# test-cell-one-shot-rev2.net
KiCad netlist of a schematic drawn in EAGLE
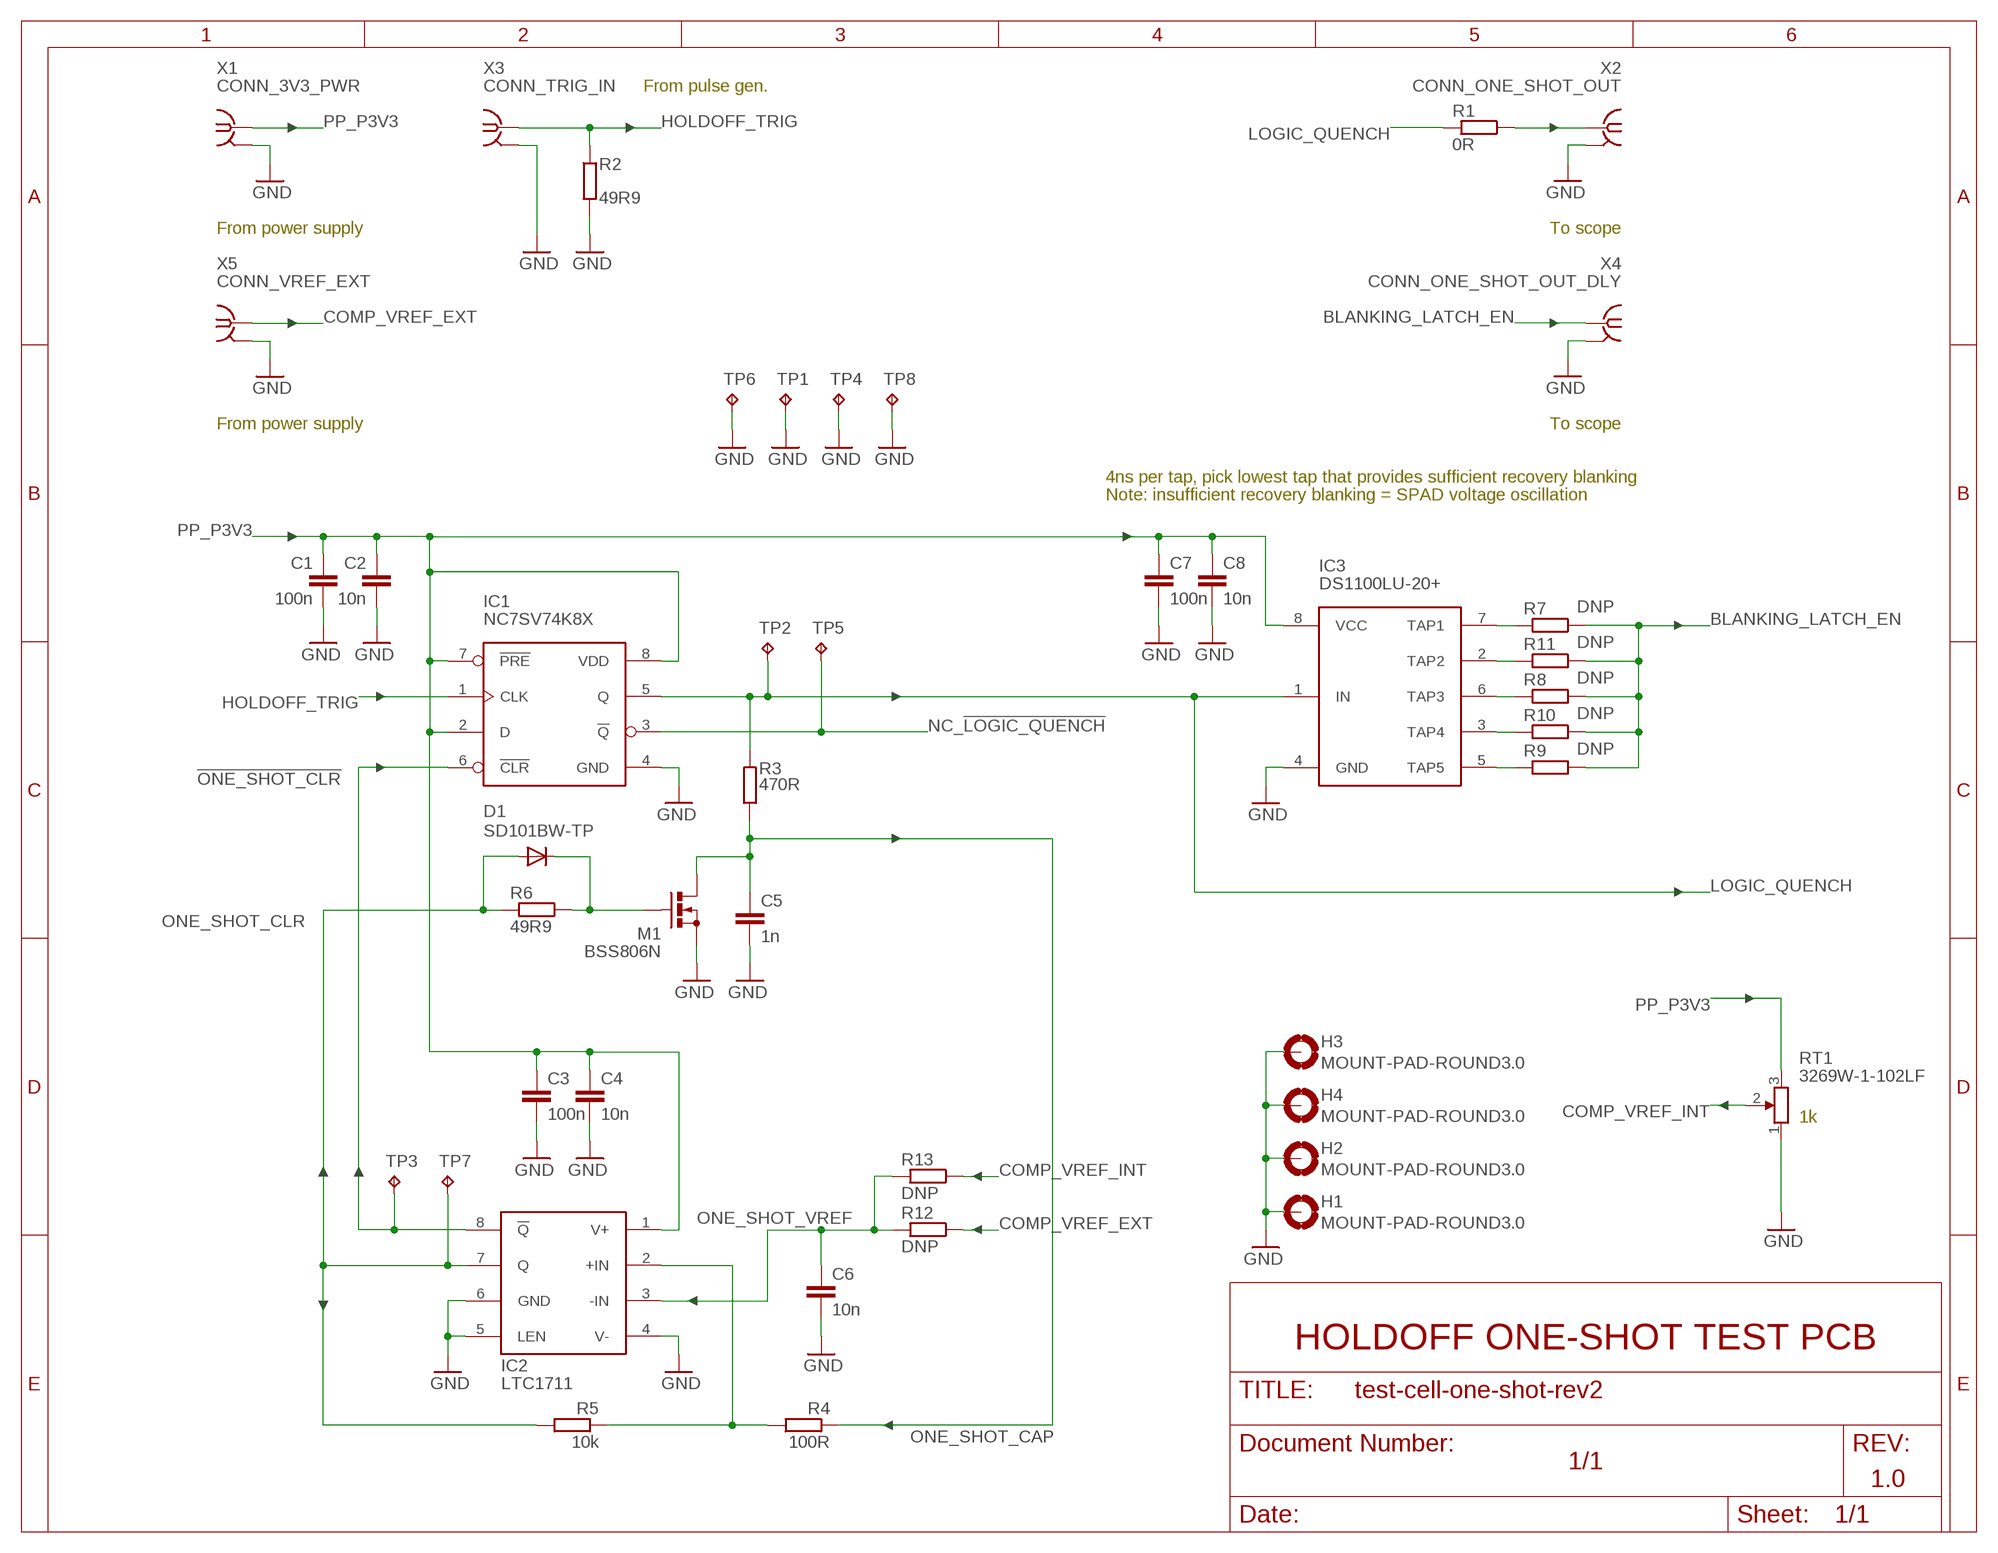
[diagram p0: schematic, sheet 1]

(export (version "E")
  (design (tool "Eeschema 10.0.6"))
  (components
    (comp (ref "C1")
      (value "100n")
      (footprint "eagle-import:C0402")
      (libsource (lib "eagle-import") (part "C-EUC0402"))
    )
    (comp (ref "C2")
      (value "10n")
      (footprint "eagle-import:C0402")
      (libsource (lib "eagle-import") (part "C-EUC0402"))
    )
    (comp (ref "C3")
      (value "100n")
      (footprint "eagle-import:C0402")
      (libsource (lib "eagle-import") (part "C-EUC0402"))
    )
    (comp (ref "C4")
      (value "10n")
      (footprint "eagle-import:C0402")
      (libsource (lib "eagle-import") (part "C-EUC0402"))
    )
    (comp (ref "C5")
      (value "1n")
      (footprint "eagle-import:C0402")
      (libsource (lib "eagle-import") (part "C-EUC0402"))
    )
    (comp (ref "C6")
      (value "10n")
      (footprint "eagle-import:C0402")
      (libsource (lib "eagle-import") (part "C-EUC0402"))
    )
    (comp (ref "C7")
      (value "100n")
      (footprint "eagle-import:C0402")
      (libsource (lib "eagle-import") (part "C-EUC0402"))
    )
    (comp (ref "C8")
      (value "10n")
      (footprint "eagle-import:C0402")
      (libsource (lib "eagle-import") (part "C-EUC0402"))
    )
    (comp (ref "D1")
      (value "SD101BW-TP")
      (footprint "eagle-import:SOD123")
      (libsource (lib "eagle-import") (part "DIODE-SOD123"))
    )
    (comp (ref "H1")
      (value "MOUNT-PAD-ROUND3.0")
      (footprint "eagle-import:3,0-PAD")
      (libsource (lib "eagle-import") (part "MOUNT-PAD-ROUND3.0"))
    )
    (comp (ref "H2")
      (value "MOUNT-PAD-ROUND3.0")
      (footprint "eagle-import:3,0-PAD")
      (libsource (lib "eagle-import") (part "MOUNT-PAD-ROUND3.0"))
    )
    (comp (ref "H3")
      (value "MOUNT-PAD-ROUND3.0")
      (footprint "eagle-import:3,0-PAD")
      (libsource (lib "eagle-import") (part "MOUNT-PAD-ROUND3.0"))
    )
    (comp (ref "H4")
      (value "MOUNT-PAD-ROUND3.0")
      (footprint "eagle-import:3,0-PAD")
      (libsource (lib "eagle-import") (part "MOUNT-PAD-ROUND3.0"))
    )
    (comp (ref "IC1")
      (value "NC7SV74K8X")
      (footprint "eagle-import:US8_3.1MM_JDEC_MO-187")
      (libsource (lib "eagle-import") (part "NC7SV74K8X"))
    )
    (comp (ref "IC2")
      (value "LTC1711")
      (footprint "eagle-import:MSOP8")
      (libsource (lib "eagle-import") (part "LTC1711"))
    )
    (comp (ref "IC3")
      (value "DS1100LU-20+")
      (footprint "eagle-import:MSOP8")
      (libsource (lib "eagle-import") (part "DS1100L"))
    )
    (comp (ref "M1")
      (value "BSS806N")
      (footprint "eagle-import:SOT23R_INFINEON")
      (libsource (lib "eagle-import") (part "BSS806N"))
    )
    (comp (ref "R1")
      (value "0R")
      (footprint "eagle-import:R0402")
      (libsource (lib "eagle-import") (part "R-EU_R0402"))
    )
    (comp (ref "R2")
      (value "49R9")
      (footprint "eagle-import:R0603")
      (libsource (lib "eagle-import") (part "R-EU_R0603"))
    )
    (comp (ref "R3")
      (value "470R")
      (footprint "eagle-import:R0402")
      (libsource (lib "eagle-import") (part "R-EU_R0402"))
    )
    (comp (ref "R4")
      (value "100R")
      (footprint "eagle-import:R0402")
      (libsource (lib "eagle-import") (part "R-EU_R0402"))
    )
    (comp (ref "R5")
      (value "10k")
      (footprint "eagle-import:R0402")
      (libsource (lib "eagle-import") (part "R-EU_R0402"))
    )
    (comp (ref "R6")
      (value "49R9")
      (footprint "eagle-import:R0402")
      (libsource (lib "eagle-import") (part "R-EU_R0402"))
    )
    (comp (ref "R7")
      (value "DNP")
      (footprint "eagle-import:R0402")
      (libsource (lib "eagle-import") (part "R-EU_R0402"))
    )
    (comp (ref "R8")
      (value "DNP")
      (footprint "eagle-import:R0402")
      (libsource (lib "eagle-import") (part "R-EU_R0402"))
    )
    (comp (ref "R9")
      (value "DNP")
      (footprint "eagle-import:R0402")
      (libsource (lib "eagle-import") (part "R-EU_R0402"))
    )
    (comp (ref "R10")
      (value "DNP")
      (footprint "eagle-import:R0402")
      (libsource (lib "eagle-import") (part "R-EU_R0402"))
    )
    (comp (ref "R11")
      (value "DNP")
      (footprint "eagle-import:R0402")
      (libsource (lib "eagle-import") (part "R-EU_R0402"))
    )
    (comp (ref "R12")
      (value "DNP")
      (footprint "eagle-import:R0402")
      (libsource (lib "eagle-import") (part "R-EU_R0402"))
    )
    (comp (ref "R13")
      (value "DNP")
      (footprint "eagle-import:R0402")
      (libsource (lib "eagle-import") (part "R-EU_R0402"))
    )
    (comp (ref "RT1")
      (value "3269W-1-102LF")
      (footprint "eagle-import:3269W")
      (libsource (lib "eagle-import") (part "BOURNS_3269WX"))
    )
    (comp (ref "TP1")
      (value "TPTP10R")
      (footprint "eagle-import:TP10R")
      (libsource (lib "eagle-import") (part "TPTP10R"))
    )
    (comp (ref "TP2")
      (value "TPTP10R")
      (footprint "eagle-import:TP10R")
      (libsource (lib "eagle-import") (part "TPTP10R"))
    )
    (comp (ref "TP3")
      (value "TPTP10R")
      (footprint "eagle-import:TP10R")
      (libsource (lib "eagle-import") (part "TPTP10R"))
    )
    (comp (ref "TP4")
      (value "TPTP10R")
      (footprint "eagle-import:TP10R")
      (libsource (lib "eagle-import") (part "TPTP10R"))
    )
    (comp (ref "TP5")
      (value "TPTP10R")
      (footprint "eagle-import:TP10R")
      (libsource (lib "eagle-import") (part "TPTP10R"))
    )
    (comp (ref "TP6")
      (value "TPTP10R")
      (footprint "eagle-import:TP10R")
      (libsource (lib "eagle-import") (part "TPTP10R"))
    )
    (comp (ref "TP7")
      (value "TPTP10R")
      (footprint "eagle-import:TP10R")
      (libsource (lib "eagle-import") (part "TPTP10R"))
    )
    (comp (ref "TP8")
      (value "TPTP10R")
      (footprint "eagle-import:TP10R")
      (libsource (lib "eagle-import") (part "TPTP10R"))
    )
    (comp (ref "X1")
      (value "CONN_3V3_PWR")
      (footprint "eagle-import:J502-ND-142-0711-871_876")
      (fields (field (name "MF") "JOHNSON COMPONENTS") (field (name "MPN") "142-0711-871"))
      (libsource (lib "eagle-import") (part "SMA-142-0711-871/876"))
    )
    (comp (ref "X2")
      (value "CONN_ONE_SHOT_OUT")
      (footprint "eagle-import:J502-ND-142-0711-871_876")
      (fields (field (name "MF") "JOHNSON COMPONENTS") (field (name "MPN") "142-0711-871"))
      (libsource (lib "eagle-import") (part "SMA-142-0711-871/876"))
    )
    (comp (ref "X3")
      (value "CONN_TRIG_IN")
      (footprint "eagle-import:J502-ND-142-0711-871_876")
      (fields (field (name "MF") "JOHNSON COMPONENTS") (field (name "MPN") "142-0711-871"))
      (libsource (lib "eagle-import") (part "SMA-142-0711-871/876"))
    )
    (comp (ref "X4")
      (value "CONN_ONE_SHOT_OUT_DLY")
      (footprint "eagle-import:J502-ND-142-0711-871_876")
      (fields (field (name "MF") "JOHNSON COMPONENTS") (field (name "MPN") "142-0711-871"))
      (libsource (lib "eagle-import") (part "SMA-142-0711-871/876"))
    )
    (comp (ref "X5")
      (value "CONN_VREF_EXT")
      (footprint "eagle-import:J502-ND-142-0711-871_876")
      (fields (field (name "MF") "JOHNSON COMPONENTS") (field (name "MPN") "142-0711-871"))
      (libsource (lib "eagle-import") (part "SMA-142-0711-871/876"))
    )
  )
  (nets
    (net (code "1") (name "/BLANKING_LATCH_EN") (class "Default")
      (node (ref "R10") (pin "1") (pinfunction "1_1") (pintype "passive"))
      (node (ref "R11") (pin "1") (pinfunction "1_1") (pintype "passive"))
      (node (ref "R7") (pin "1") (pinfunction "1_1") (pintype "passive"))
      (node (ref "R8") (pin "1") (pinfunction "1_1") (pintype "passive"))
      (node (ref "R9") (pin "1") (pinfunction "1_1") (pintype "passive"))
      (node (ref "X4") (pin "1") (pinfunction "1_1") (pintype "passive"))
    )
    (net (code "2") (name "/COMP_VREF_EXT") (class "Default")
      (node (ref "R12") (pin "1") (pinfunction "1_1") (pintype "passive"))
      (node (ref "X5") (pin "1") (pinfunction "1_1") (pintype "passive"))
    )
    (net (code "3") (name "/COMP_VREF_INT") (class "Default")
      (node (ref "R13") (pin "1") (pinfunction "1_1") (pintype "passive"))
      (node (ref "RT1") (pin "2") (pinfunction "2_2") (pintype "bidirectional"))
    )
    (net (code "4") (name "/HOLDOFF_TRIG") (class "Default")
      (node (ref "IC1") (pin "1") (pinfunction "CLK_1") (pintype "bidirectional"))
      (node (ref "R2") (pin "1") (pinfunction "1_1") (pintype "passive"))
      (node (ref "X3") (pin "1") (pinfunction "1_1") (pintype "passive"))
    )
    (net (code "5") (name "/LOGIC_QUENCH") (class "Default")
      (node (ref "IC1") (pin "5") (pinfunction "Q_5") (pintype "bidirectional"))
      (node (ref "IC3") (pin "1") (pinfunction "IN_1") (pintype "bidirectional"))
      (node (ref "R1") (pin "2") (pinfunction "2_2") (pintype "passive"))
      (node (ref "R3") (pin "2") (pinfunction "2_2") (pintype "passive"))
      (node (ref "TP2") (pin "TP") (pinfunction "TP_TP") (pintype "input"))
    )
    (net (code "6") (name "/NC_~{LOGIC_QUENCH}") (class "Default")
      (node (ref "IC1") (pin "3") (pinfunction "~{Q}_3") (pintype "bidirectional"))
      (node (ref "TP5") (pin "TP") (pinfunction "TP_TP") (pintype "input"))
    )
    (net (code "7") (name "/ONE_SHOT_CAP") (class "Default")
      (node (ref "C5") (pin "1") (pinfunction "1_1") (pintype "passive"))
      (node (ref "M1") (pin "3") (pinfunction "D_3") (pintype "passive"))
      (node (ref "R3") (pin "1") (pinfunction "1_1") (pintype "passive"))
      (node (ref "R4") (pin "2") (pinfunction "2_2") (pintype "passive"))
    )
    (net (code "8") (name "/ONE_SHOT_CLR") (class "Default")
      (node (ref "D1") (pin "A") (pinfunction "A_A") (pintype "passive"))
      (node (ref "IC2") (pin "7") (pinfunction "Q_7") (pintype "bidirectional"))
      (node (ref "R5") (pin "1") (pinfunction "1_1") (pintype "passive"))
      (node (ref "R6") (pin "2") (pinfunction "2_2") (pintype "passive"))
      (node (ref "TP7") (pin "TP") (pinfunction "TP_TP") (pintype "input"))
    )
    (net (code "9") (name "/ONE_SHOT_VREF") (class "Default")
      (node (ref "C6") (pin "1") (pinfunction "1_1") (pintype "passive"))
      (node (ref "IC2") (pin "3") (pinfunction "-IN_3") (pintype "bidirectional"))
      (node (ref "R12") (pin "2") (pinfunction "2_2") (pintype "passive"))
      (node (ref "R13") (pin "2") (pinfunction "2_2") (pintype "passive"))
    )
    (net (code "10") (name "/PP_P3V3") (class "Default")
      (node (ref "C1") (pin "1") (pinfunction "1_1") (pintype "passive"))
      (node (ref "C2") (pin "1") (pinfunction "1_1") (pintype "passive"))
      (node (ref "C3") (pin "1") (pinfunction "1_1") (pintype "passive"))
      (node (ref "C4") (pin "1") (pinfunction "1_1") (pintype "passive"))
      (node (ref "C7") (pin "1") (pinfunction "1_1") (pintype "passive"))
      (node (ref "C8") (pin "1") (pinfunction "1_1") (pintype "passive"))
      (node (ref "IC1") (pin "2") (pinfunction "D_2") (pintype "bidirectional"))
      (node (ref "IC1") (pin "7") (pinfunction "~{PRE}_7") (pintype "bidirectional"))
      (node (ref "IC1") (pin "8") (pinfunction "VDD_8") (pintype "bidirectional"))
      (node (ref "IC2") (pin "1") (pinfunction "V+_1") (pintype "bidirectional"))
      (node (ref "IC3") (pin "8") (pinfunction "VCC_8") (pintype "bidirectional"))
      (node (ref "RT1") (pin "3") (pinfunction "3_3") (pintype "bidirectional"))
      (node (ref "X1") (pin "1") (pinfunction "1_1") (pintype "passive"))
    )
    (net (code "11") (name "/~{ONE_SHOT_CLR}") (class "Default")
      (node (ref "IC1") (pin "6") (pinfunction "~{CLR}_6") (pintype "bidirectional"))
      (node (ref "IC2") (pin "8") (pinfunction "~{Q}_8") (pintype "bidirectional"))
      (node (ref "TP3") (pin "TP") (pinfunction "TP_TP") (pintype "input"))
    )
    (net (code "12") (name "GND") (class "Default")
      (node (ref "C1") (pin "2") (pinfunction "2_2") (pintype "passive"))
      (node (ref "C2") (pin "2") (pinfunction "2_2") (pintype "passive"))
      (node (ref "C3") (pin "2") (pinfunction "2_2") (pintype "passive"))
      (node (ref "C4") (pin "2") (pinfunction "2_2") (pintype "passive"))
      (node (ref "C5") (pin "2") (pinfunction "2_2") (pintype "passive"))
      (node (ref "C6") (pin "2") (pinfunction "2_2") (pintype "passive"))
      (node (ref "C7") (pin "2") (pinfunction "2_2") (pintype "passive"))
      (node (ref "C8") (pin "2") (pinfunction "2_2") (pintype "passive"))
      (node (ref "H1") (pin "B3,0") (pinfunction "MOUNT_B3,0") (pintype "passive"))
      (node (ref "H2") (pin "B3,0") (pinfunction "MOUNT_B3,0") (pintype "passive"))
      (node (ref "H3") (pin "B3,0") (pinfunction "MOUNT_B3,0") (pintype "passive"))
      (node (ref "H4") (pin "B3,0") (pinfunction "MOUNT_B3,0") (pintype "passive"))
      (node (ref "IC1") (pin "4") (pinfunction "GND_4") (pintype "bidirectional"))
      (node (ref "IC2") (pin "4") (pinfunction "V-_4") (pintype "bidirectional"))
      (node (ref "IC2") (pin "5") (pinfunction "LEN_5") (pintype "bidirectional"))
      (node (ref "IC2") (pin "6") (pinfunction "GND_6") (pintype "bidirectional"))
      (node (ref "IC3") (pin "4") (pinfunction "GND_4") (pintype "bidirectional"))
      (node (ref "M1") (pin "2") (pinfunction "S_2") (pintype "passive"))
      (node (ref "R2") (pin "2") (pinfunction "2_2") (pintype "passive"))
      (node (ref "RT1") (pin "1") (pinfunction "1_1") (pintype "bidirectional"))
      (node (ref "TP1") (pin "TP") (pinfunction "TP_TP") (pintype "input"))
      (node (ref "TP4") (pin "TP") (pinfunction "TP_TP") (pintype "input"))
      (node (ref "TP6") (pin "TP") (pinfunction "TP_TP") (pintype "input"))
      (node (ref "TP8") (pin "TP") (pinfunction "TP_TP") (pintype "input"))
      (node (ref "X1") (pin "G@1") (pinfunction "GND_G@1") (pintype "power_in"))
      (node (ref "X2") (pin "G@1") (pinfunction "GND_G@1") (pintype "power_in"))
      (node (ref "X3") (pin "G@1") (pinfunction "GND_G@1") (pintype "power_in"))
      (node (ref "X4") (pin "G@1") (pinfunction "GND_G@1") (pintype "power_in"))
      (node (ref "X5") (pin "G@1") (pinfunction "GND_G@1") (pintype "power_in"))
    )
    (net (code "13") (name "Net-(IC2-+IN)") (class "Default")
      (node (ref "IC2") (pin "2") (pinfunction "+IN_2") (pintype "bidirectional"))
      (node (ref "R4") (pin "1") (pinfunction "1_1") (pintype "passive"))
      (node (ref "R5") (pin "2") (pinfunction "2_2") (pintype "passive"))
    )
    (net (code "14") (name "Net-(IC3-TAP1)") (class "Default")
      (node (ref "IC3") (pin "7") (pinfunction "TAP1_7") (pintype "bidirectional"))
      (node (ref "R7") (pin "2") (pinfunction "2_2") (pintype "passive"))
    )
    (net (code "15") (name "Net-(IC3-TAP2)") (class "Default")
      (node (ref "IC3") (pin "2") (pinfunction "TAP2_2") (pintype "bidirectional"))
      (node (ref "R11") (pin "2") (pinfunction "2_2") (pintype "passive"))
    )
    (net (code "16") (name "Net-(IC3-TAP3)") (class "Default")
      (node (ref "IC3") (pin "6") (pinfunction "TAP3_6") (pintype "bidirectional"))
      (node (ref "R8") (pin "2") (pinfunction "2_2") (pintype "passive"))
    )
    (net (code "17") (name "Net-(IC3-TAP4)") (class "Default")
      (node (ref "IC3") (pin "3") (pinfunction "TAP4_3") (pintype "bidirectional"))
      (node (ref "R10") (pin "2") (pinfunction "2_2") (pintype "passive"))
    )
    (net (code "18") (name "Net-(IC3-TAP5)") (class "Default")
      (node (ref "IC3") (pin "5") (pinfunction "TAP5_5") (pintype "bidirectional"))
      (node (ref "R9") (pin "2") (pinfunction "2_2") (pintype "passive"))
    )
    (net (code "19") (name "Net-(M1-G)") (class "Default")
      (node (ref "D1") (pin "C") (pinfunction "C_C") (pintype "passive"))
      (node (ref "M1") (pin "1") (pinfunction "G_1") (pintype "passive"))
      (node (ref "R6") (pin "1") (pinfunction "1_1") (pintype "passive"))
    )
    (net (code "20") (name "Net-(R1-Pad1)") (class "Default")
      (node (ref "R1") (pin "1") (pinfunction "1_1") (pintype "passive"))
      (node (ref "X2") (pin "1") (pinfunction "1_1") (pintype "passive"))
    )
  )
)
